# Power_Supply.net
KiCad netlist of a schematic drawn in Altium Designer
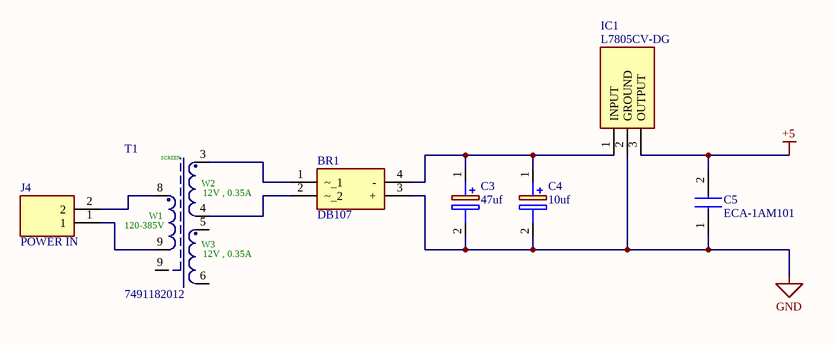
[diagram p0: Power Supply.SchDoc]

(export (version "E")
  (design (tool "Eeschema 10.0.6"))
  (components
    (comp (ref "BR1")
      (value "DB107")
      (footprint "SamacSys:DIP825W50P510L830H340Q4N")
      (description "Bridge Rectifier")
      (fields (field (name "MOUSER PART NUMBER") "583-DB107"))
      (libsource (lib "*") (part "DB107"))
    )
    (comp (ref "C3")
      (value "47uf")
      (footprint "SamacSys:CAPPRD250W55D630H1220")
      (description "Capacitor Polarised")
      (fields
        (field (name "MANUFACTURER_PART_NUMBER") "ECE-A1EN470UB")
        (field (name "MOUSER PART NUMBER") "667-ECE-A1EN470UB")
      )
      (libsource (lib "*") (part "ECE-A1EN470UB"))
    )
    (comp (ref "C4")
      (value "10uf")
      (footprint "SamacSys:CAPPRD200W55D500H1200")
      (description "Capacitor Polarised")
      (fields
        (field (name "MANUFACTURER_PART_NUMBER") "ECA-1EM100")
        (field (name "MOUSER PART NUMBER") "667-ECA-1EM100")
      )
      (libsource (lib "*") (part "ECA-1EM100"))
    )
    (comp (ref "C5")
      (value "ECA-1AM101")
      (footprint "SamacSys:CAPPRD200W55D525H1200")
      (description "Capacitor")
      (fields (field (name "MOUSER PART NUMBER") "667-ECA-1AM101"))
      (libsource (lib "*") (part "ECA-1AM101"))
    )
    (comp (ref "IC1")
      (value "L7805CV-DG")
      (footprint "SamacSys:TO255P460X1020X2008-3P")
      (description "Integrated Circuit")
      (fields (field (name "MOUSER PART NUMBER") "511-L7805CV-DG"))
      (libsource (lib "*") (part "L7805CV-DG"))
    )
    (comp (ref "J4")
      (value "POWER IN")
      (footprint "SamacSys:TB00250002BE")
      (description "Connector")
      (fields
        (field (name "MANUFACTURER_PART_NUMBER") "TB002-500-02BE")
        (field (name "MOUSER PART NUMBER") "490-TB002-500-02BE")
      )
      (libsource (lib "*") (part "TB002-500-02BE"))
    )
    (comp (ref "T1")
      (value "7491182012")
      (footprint "EE16_7_4 (E16)")
      (description "Off-Line Transformer WE-UNIT , L=0.9mH")
      (fields (field (name "MANUFACTURER") "Wuerth Elektronik"))
      (libsource (lib "Altium Content Vault") (part "WE-7491182012"))
    )
  )
  (nets
    (net (code "1") (name "+5") (class "Default")
      (node (ref "C5") (pin "2") (pinfunction "-_2") (pintype "passive"))
      (node (ref "IC1") (pin "3") (pinfunction "OUTPUT_3") (pintype "passive"))
    )
    (net (code "2") (name "GND") (class "Default")
      (node (ref "BR1") (pin "3") (pinfunction "+_3") (pintype "passive"))
      (node (ref "C3") (pin "2") (pinfunction "-_2") (pintype "passive"))
      (node (ref "C4") (pin "2") (pinfunction "-_2") (pintype "passive"))
      (node (ref "C5") (pin "1") (pinfunction "+_1") (pintype "passive"))
      (node (ref "IC1") (pin "2") (pinfunction "GROUND_2") (pintype "passive"))
    )
    (net (code "3") (name "Net-(BR1--)") (class "Default")
      (node (ref "BR1") (pin "4") (pinfunction "-_4") (pintype "passive"))
      (node (ref "C3") (pin "1") (pinfunction "+_1") (pintype "passive"))
      (node (ref "C4") (pin "1") (pinfunction "+_1") (pintype "passive"))
      (node (ref "IC1") (pin "1") (pinfunction "INPUT_1") (pintype "passive"))
    )
    (net (code "4") (name "Net-(BR1-~_1)") (class "Default")
      (node (ref "BR1") (pin "1") (pinfunction "~_1_1") (pintype "passive"))
      (node (ref "T1") (pin "3") (pinfunction "3_3") (pintype "passive"))
    )
    (net (code "5") (name "Net-(BR1-~_2)") (class "Default")
      (node (ref "BR1") (pin "2") (pinfunction "~_2_2") (pintype "passive"))
      (node (ref "T1") (pin "4") (pinfunction "4_4") (pintype "passive"))
    )
    (net (code "6") (name "Net-(J4-Pad1)") (class "Default")
      (node (ref "J4") (pin "1") (pinfunction "1_1") (pintype "passive"))
      (node (ref "T1") (pin "9") (pinfunction "9_9") (pintype "passive"))
    )
    (net (code "7") (name "Net-(J4-Pad2)") (class "Default")
      (node (ref "J4") (pin "2") (pinfunction "2_2") (pintype "passive"))
      (node (ref "T1") (pin "8") (pinfunction "8_8") (pintype "passive"))
    )
    (net (code "8") (name "unconnected-(T1-Pad5)") (class "Default")
      (node (ref "T1") (pin "5") (pinfunction "5_5") (pintype "passive"))
    )
    (net (code "9") (name "unconnected-(T1-Pad6)") (class "Default")
      (node (ref "T1") (pin "6") (pinfunction "6_6") (pintype "passive"))
    )
    (net (code "10") (name "unconnected-(T1-Pad9)") (class "Default")
      (node (ref "T1") (pin "9") (pinfunction "9_9") (pintype "passive"))
    )
  )
)
